# Sheet1.net
KiCad netlist of a schematic drawn in Altium Designer
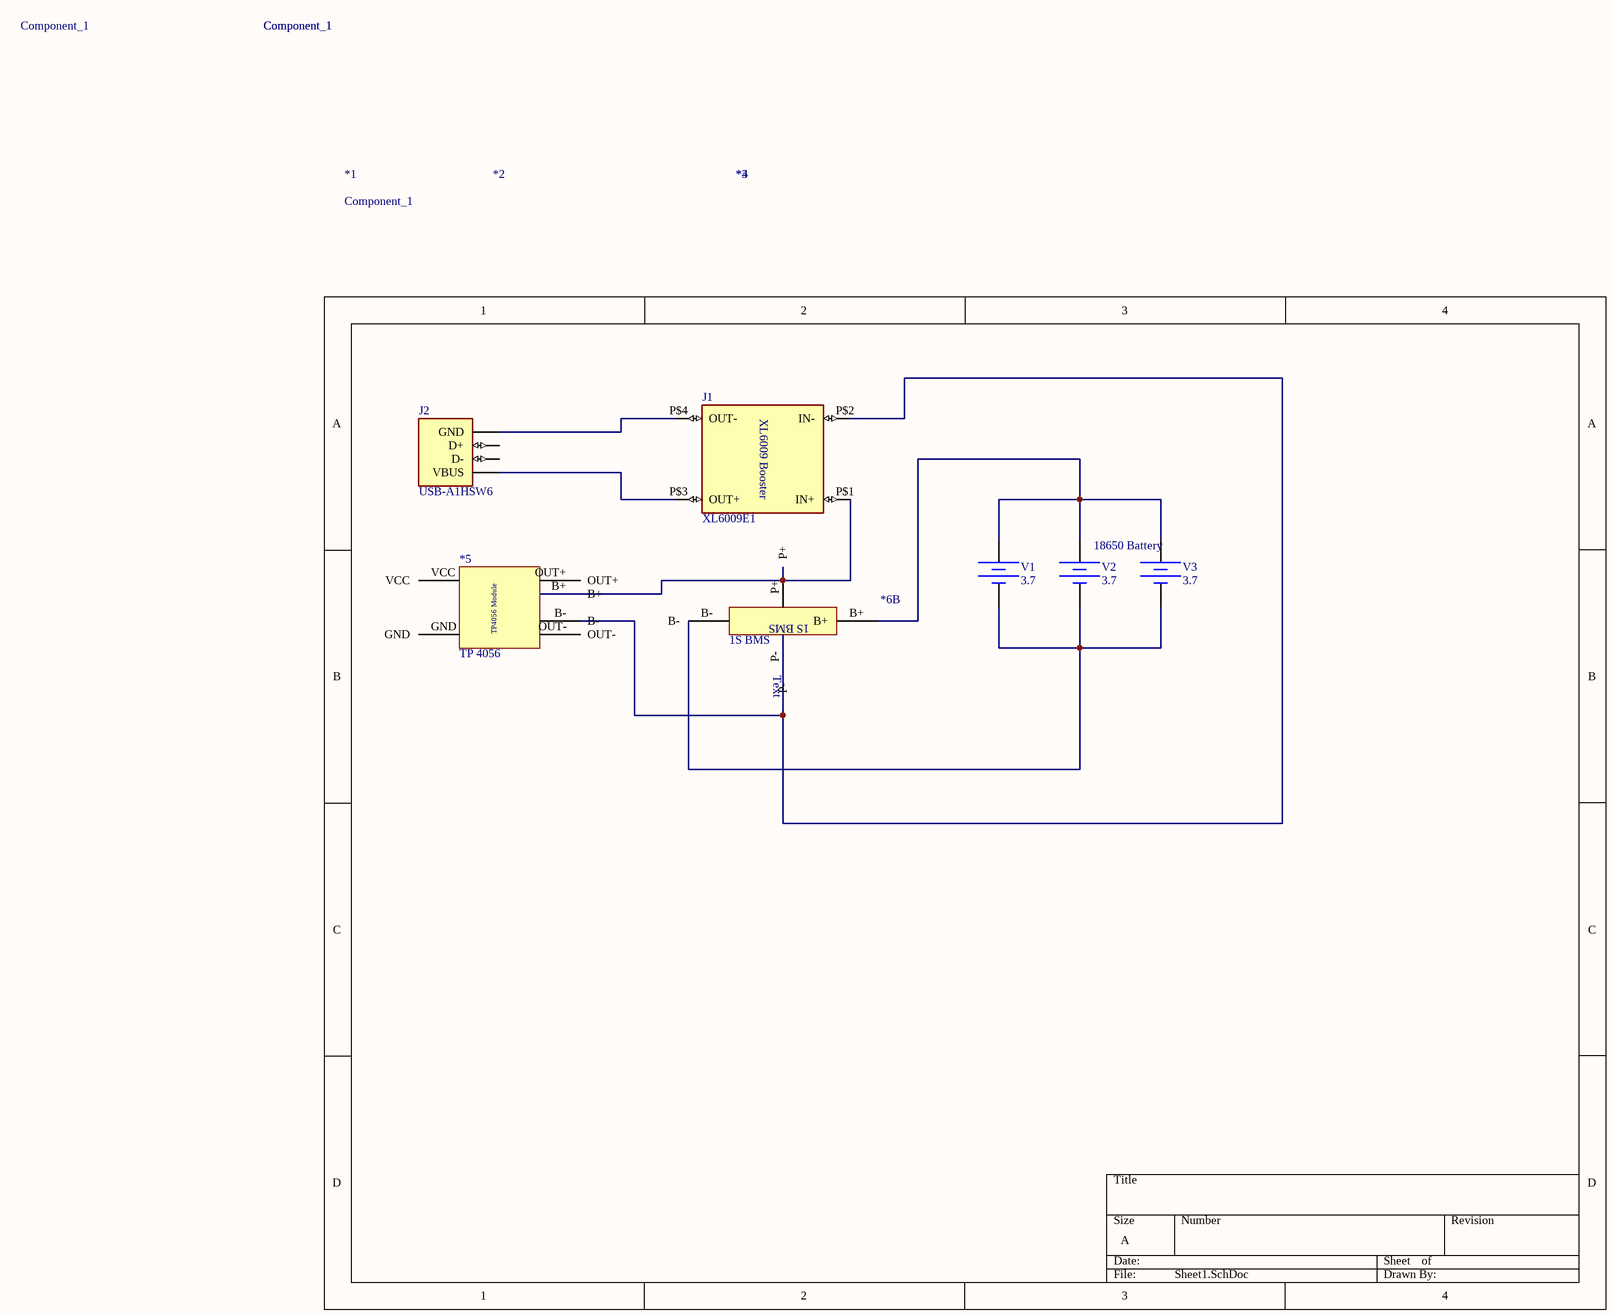
[diagram p0: Sheet1.SchDoc]

(export (version "E")
  (design (tool "Eeschema 10.0.6"))
  (components
    (comp (ref "*1") (value "Component_1") (libsource (lib "Schlib1") (part "Component_1")))
    (comp (ref "*2") (value "Component_1") (libsource (lib "Schlib1") (part "Component_1")))
    (comp (ref "*3") (value "Component_1") (libsource (lib "Schlib1") (part "Component_1")))
    (comp (ref "*4") (value "Component_1") (libsource (lib "Schlib1") (part "Component_1")))
    (comp (ref "*5") (value "TP 4056") (libsource (lib "TP4056_Module") (part "Component_1")))
    (comp (ref "*6") (value "1S BMS") (libsource (lib "BMS_1S") (part "Component_1")))
    (comp (ref "J1")
      (value "XL6009E1")
      (footprint "XL6009E1")
      (description "400KHz 60V 4A Switching Current Boost / Buck-Boost / Inverting DC/DC Converter")
      (fields (field (name "MF") "XLSEMI"))
      (libsource (lib "XL6009E1") (part "XL6009E1"))
    )
    (comp (ref "J2")
      (value "USB-A1HSW6")
      (footprint "OST_USB-A1HSW6")
      (fields (field (name "MF") "{'manufacturer': u'On Shore Technology Inc.'}"))
      (libsource (lib "USB-A1HSW6") (part "USB-A1HSW6"))
    )
    (comp (ref "V1")
      (value "Constant Voltage Source")
      (fields (field (name "DC MAGNITUDE") "3.7"))
      (libsource (lib "Simulation Generic Components") (part "Battery"))
    )
    (comp (ref "V2")
      (value "Constant Voltage Source")
      (fields (field (name "DC MAGNITUDE") "3.7"))
      (libsource (lib "Simulation Generic Components") (part "Battery"))
    )
    (comp (ref "V3")
      (value "Constant Voltage Source")
      (fields (field (name "DC MAGNITUDE") "3.7"))
      (libsource (lib "Simulation Generic Components") (part "Battery"))
    )
  )
  (nets
    (net (code "1") (name "Net-(*6-PadB+)") (class "Default")
      (node (ref "*6") (pin "B+") (pinfunction "B+_B+") (pintype "passive"))
      (node (ref "V1") (pin "1") (pinfunction "1_1") (pintype "passive"))
      (node (ref "V2") (pin "1") (pinfunction "1_1") (pintype "passive"))
      (node (ref "V3") (pin "1") (pinfunction "1_1") (pintype "passive"))
    )
    (net (code "2") (name "Net-(J1-IN+)") (class "Default")
      (node (ref "*5") (pin "B+") (pinfunction "B+_B+") (pintype "passive"))
      (node (ref "J1") (pin "P$1") (pinfunction "IN+_P$1") (pintype "bidirectional"))
    )
    (net (code "3") (name "Net-(J1-IN-)") (class "Default")
      (node (ref "*6") (pin "P-") (pinfunction "P-_P-") (pintype "passive"))
      (node (ref "J1") (pin "P$2") (pinfunction "IN-_P$2") (pintype "bidirectional"))
    )
    (net (code "4") (name "Net-(J1-OUT+)") (class "Default")
      (node (ref "J1") (pin "P$3") (pinfunction "OUT+_P$3") (pintype "bidirectional"))
      (node (ref "J2") (pin "1") (pinfunction "VBUS_1") (pintype "power_in"))
    )
    (net (code "5") (name "Net-(J1-OUT-)") (class "Default")
      (node (ref "J1") (pin "P$4") (pinfunction "OUT-_P$4") (pintype "bidirectional"))
      (node (ref "J2") (pin "4") (pinfunction "GND_4") (pintype "power_in"))
    )
    (net (code "6") (name "Net-(V1-Pad2)") (class "Default")
      (node (ref "V1") (pin "2") (pinfunction "2_2") (pintype "passive"))
      (node (ref "V2") (pin "2") (pinfunction "2_2") (pintype "passive"))
      (node (ref "V3") (pin "2") (pinfunction "2_2") (pintype "passive"))
    )
    (net (code "7") (name "unconnected-(*5-PadB-)") (class "Default")
      (node (ref "*5") (pin "B-") (pinfunction "B-_B-") (pintype "passive"))
    )
    (net (code "8") (name "unconnected-(*5-PadGND)") (class "Default")
      (node (ref "*5") (pin "GND") (pinfunction "GND_GND") (pintype "passive"))
    )
    (net (code "9") (name "unconnected-(*5-PadOUT+)") (class "Default")
      (node (ref "*5") (pin "OUT+") (pinfunction "OUT+_OUT+") (pintype "passive"))
    )
    (net (code "10") (name "unconnected-(*5-PadOUT-)") (class "Default")
      (node (ref "*5") (pin "OUT-") (pinfunction "OUT-_OUT-") (pintype "passive"))
    )
    (net (code "11") (name "unconnected-(*5-PadVCC)") (class "Default")
      (node (ref "*5") (pin "VCC") (pinfunction "VCC_VCC") (pintype "passive"))
    )
    (net (code "12") (name "unconnected-(*6-PadB-)") (class "Default")
      (node (ref "*6") (pin "B-") (pinfunction "B-_B-") (pintype "passive"))
    )
    (net (code "13") (name "unconnected-(*6-PadP+)") (class "Default")
      (node (ref "*6") (pin "P+") (pinfunction "P+_P+") (pintype "passive"))
    )
    (net (code "14") (name "unconnected-(J2-D+-Pad3)") (class "Default")
      (node (ref "J2") (pin "3") (pinfunction "D+_3") (pintype "bidirectional"))
    )
    (net (code "15") (name "unconnected-(J2-D--Pad2)") (class "Default")
      (node (ref "J2") (pin "2") (pinfunction "D-_2") (pintype "bidirectional"))
    )
  )
)
